# numpad.net
KiCad netlist of a schematic drawn in Altium Designer
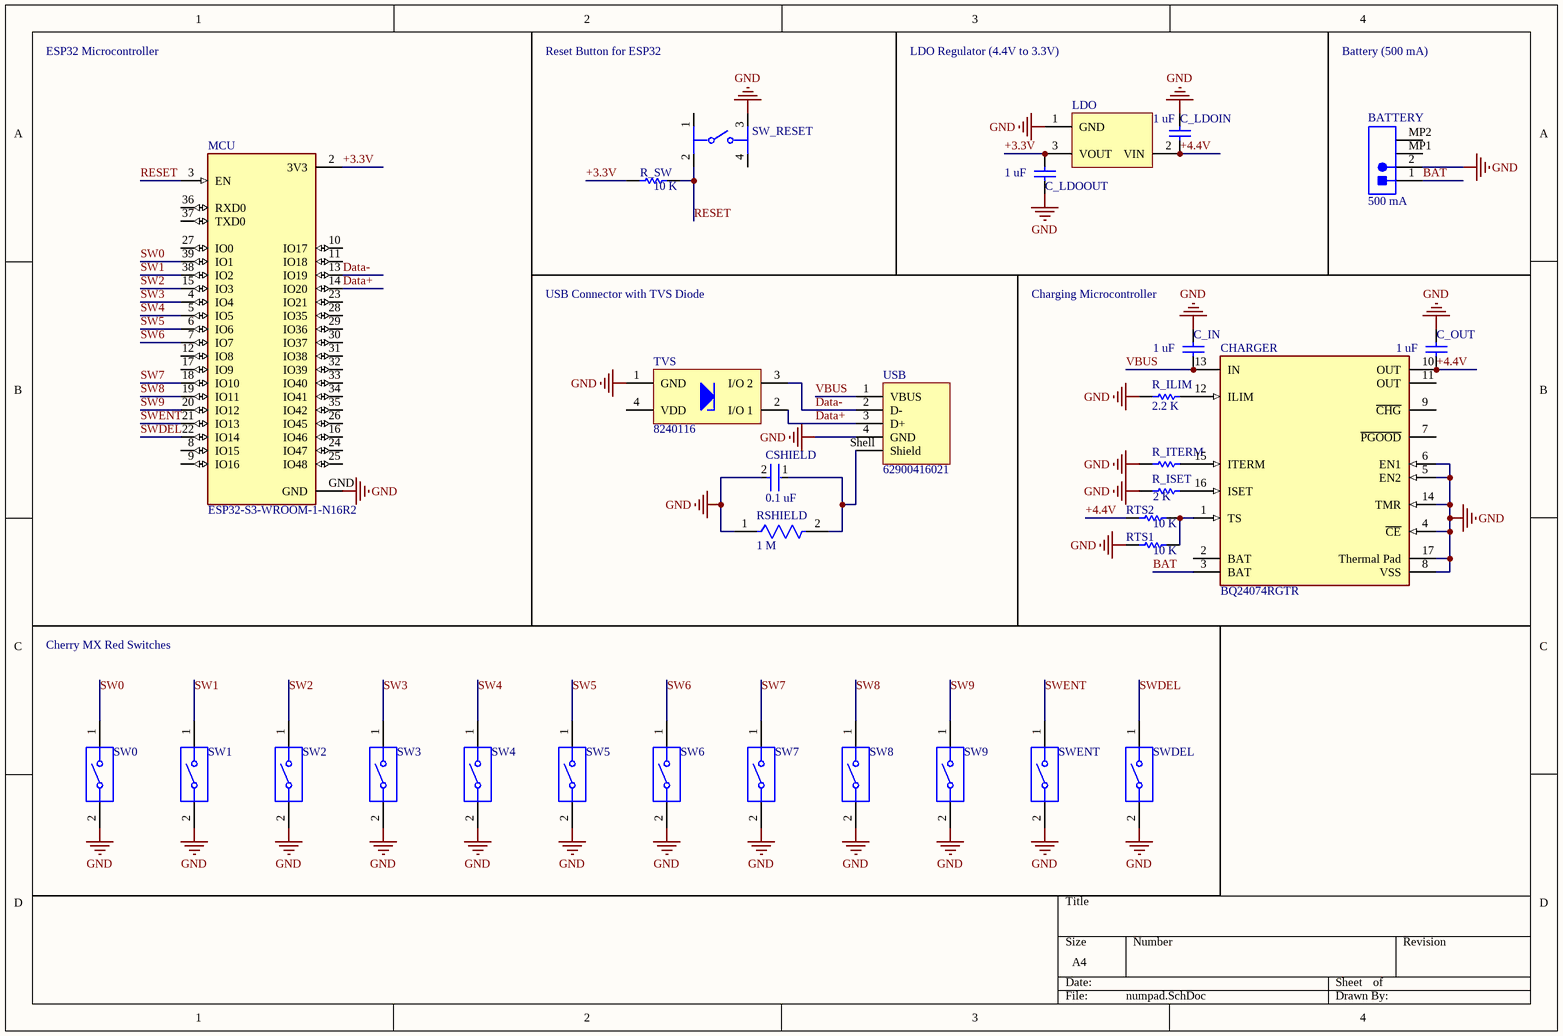
[diagram p0: numpad.SchDoc]

(export (version "E")
  (design (tool "Eeschema 10.0.6"))
  (components
    (comp (ref "BATTERY")
      (value "500 mA")
      (footprint "JST- S2B-PH-SM4-TB(LF)(SN)-2_V")
      (description "Male Header, Pitch 2 mm, 1 x 2 Position, Height 5.5 mm, -25 to 85 degC, RoHS, Tape and Reel")
      (libsource (lib "Altium Content Vault") (part "CN-1P-2M-R2"))
    )
    (comp (ref "CHARGER")
      (value "BQ24074RGTR")
      (footprint "FP-RGT0016C-IPC_B")
      (description "IC LI-ION CHARGE MGMT 16-QFN")
      (libsource (lib "Altium Content Vault") (part "bc0294d1c007ba64400ebcffad863a1"))
    )
    (comp (ref "CSHIELD")
      (value "0.1 uF")
      (footprint "FP-GRM15-MFG")
      (description "CAP CER 0.1UF 16V X7R 0402")
      (fields (field (name "MANUFACTURER PART NUMBER") "GRM155R71C104KA88D") (field (name "TOLERANCE") "10%"))
      (libsource (lib "Altium Content Vault") (part "236180d848d6139a670b325ea6854c9"))
    )
    (comp (ref "C_IN")
      (value "1 uF")
      (footprint "CAPC1608X87X35LL15T15")
      (fields (field (name "PART NUMBER") "C0603C105K3RACTU") (field (name "MANUFACTURER") "Kemet"))
      (libsource (lib "Altium Content Vault") (part "CAP"))
    )
    (comp (ref "C_LDOIN")
      (value "1 uF")
      (footprint "CAPC1608X87X35LL15T15")
      (fields (field (name "PART NUMBER") "C0603C105K3RACTU") (field (name "MANUFACTURER") "Kemet"))
      (libsource (lib "Altium Content Vault") (part "CAP"))
    )
    (comp (ref "C_LDOOUT")
      (value "1 uF")
      (footprint "CAPC1608X87X35LL15T15")
      (fields (field (name "PART NUMBER") "C0603C105K3RACTU") (field (name "MANUFACTURER") "Kemet"))
      (libsource (lib "Altium Content Vault") (part "CAP"))
    )
    (comp (ref "C_OUT")
      (value "1 uF")
      (footprint "CAPC1608X87X35LL15T15")
      (fields (field (name "PART NUMBER") "C0603C105K3RACTU") (field (name "MANUFACTURER") "Kemet"))
      (libsource (lib "Altium Content Vault") (part "CAP"))
    )
    (comp (ref "LDO")
      (value "MCP1700-3302E/TO")
      (footprint "TO-92-TO3")
      (description "Low Quiescent Current LDO, 3-Pin TO-92, Extended TemperatureBAG")
      (libsource (lib "Altium Content Vault") (part "PM-LINEREG-MCP1700-IL3B"))
    )
    (comp (ref "MCU")
      (value "ESP32-S3-WROOM-1-N16R2")
      (footprint "XCVR_ESP32-S3-WROOM-1-N16R2")
      (description "Bluetooth, WiFi 802.11b/g/n, Bluetooth v5.0 Transceiver Module 2.4GHz PCB Trace Surface Mount")
      (fields (field (name "MF") "Espressif Systems") (field (name "MP") "ESP32S3WROOM1N16R2"))
      (libsource (lib "Awab Choudhury") (part "ESP32-S3-WROOM-1-N16R2"))
    )
    (comp (ref "RSHIELD")
      (value "1 M")
      (footprint "FP-MCR01-IPC_A")
      (description "Thick Film Chip Resistor, 0402, 1MΩ, 5%, 200ppm/°C, 0.063W, 50V")
      (fields (field (name "TOLERANCE") "5%"))
      (libsource (lib "Altium Content Vault") (part "1029c3af85768c4190bb7ad29bc67b5"))
    )
    (comp (ref "RTS1")
      (value "10 K")
      (footprint "RESC1005X40X25LL05T10")
      (fields (field (name "PART NUMBER") "RC0402FR-0710KL") (field (name "MANUFACTURER") "Yageo / Phycomp"))
      (libsource (lib "Altium Content Vault") (part "RES"))
    )
    (comp (ref "RTS2")
      (value "10 K")
      (footprint "RESC1005X40X25LL05T10")
      (fields (field (name "PART NUMBER") "RC0402FR-0710KL") (field (name "MANUFACTURER") "Yageo / Phycomp"))
      (libsource (lib "Altium Content Vault") (part "RES"))
    )
    (comp (ref "R_ILIM")
      (value "2.2 K")
      (footprint "RESC1608X55X25LL10T15")
      (fields (field (name "TOLERANCE") "1%") (field (name "MANUFACTURER") "Yageo"))
      (libsource (lib "Altium Content Vault") (part "RES-2"))
    )
    (comp (ref "R_ISET")
      (value "CRCW")
      (footprint "RESC1609X50X30ML10T20")
      (fields (field (name "MANUFACTURER") "Vishay Dale") (field (name "PART NUMBER") "2 K"))
      (libsource (lib "Altium Content Vault") (part "RES"))
    )
    (comp (ref "R_ITERM")
      (value "RC04")
      (footprint "RESC1005X40X25LL05T10")
      (fields (field (name "PART NUMBER") "RC0402FR-0710KL") (field (name "MANUFACTURER") "Yageo / Phycomp"))
      (libsource (lib "Altium Content Vault") (part "RES"))
    )
    (comp (ref "R_SW")
      (value "10 K")
      (footprint "RESC1005X40X25LL05T10")
      (fields (field (name "PART NUMBER") "RC0402FR-0710KL") (field (name "MANUFACTURER") "Yageo / Phycomp"))
      (libsource (lib "Altium Content Vault") (part "RES"))
    )
    (comp (ref "SW0")
      (value "MX1A-11NW")
      (footprint "CHRY-MX1A-11NW_V")
      (description "Keylock Switch, 12 V, -10 to 70 degC, 2-Pin THD, RoHS, Bulk")
      (fields (field (name "MANUFACTURER") "Cherry") (field (name "PART NO") "MX1A11NW"))
      (libsource (lib "Altium Content Vault") (part "KEYSW-SPST-2"))
    )
    (comp (ref "SW1")
      (value "MX1A-11NW")
      (footprint "CHRY-MX1A-11NW_V")
      (description "Keylock Switch, 12 V, -10 to 70 degC, 2-Pin THD, RoHS, Bulk")
      (fields (field (name "MANUFACTURER") "Cherry") (field (name "PART NO") "MX1A11NW"))
      (libsource (lib "Altium Content Vault") (part "KEYSW-SPST-2"))
    )
    (comp (ref "SW2")
      (value "MX1A-11NW")
      (footprint "CHRY-MX1A-11NW_V")
      (description "Keylock Switch, 12 V, -10 to 70 degC, 2-Pin THD, RoHS, Bulk")
      (fields (field (name "MANUFACTURER") "Cherry") (field (name "PART NO") "MX1A11NW"))
      (libsource (lib "Altium Content Vault") (part "KEYSW-SPST-2"))
    )
    (comp (ref "SW3")
      (value "MX1A-11NW")
      (footprint "CHRY-MX1A-11NW_V")
      (description "Keylock Switch, 12 V, -10 to 70 degC, 2-Pin THD, RoHS, Bulk")
      (fields (field (name "MANUFACTURER") "Cherry") (field (name "PART NO") "MX1A11NW"))
      (libsource (lib "Altium Content Vault") (part "KEYSW-SPST-2"))
    )
    (comp (ref "SW4")
      (value "MX1A-11NW")
      (footprint "CHRY-MX1A-11NW_V")
      (description "Keylock Switch, 12 V, -10 to 70 degC, 2-Pin THD, RoHS, Bulk")
      (fields (field (name "MANUFACTURER") "Cherry") (field (name "PART NO") "MX1A11NW"))
      (libsource (lib "Altium Content Vault") (part "KEYSW-SPST-2"))
    )
    (comp (ref "SW5")
      (value "MX1A-11NW")
      (footprint "CHRY-MX1A-11NW_V")
      (description "Keylock Switch, 12 V, -10 to 70 degC, 2-Pin THD, RoHS, Bulk")
      (fields (field (name "MANUFACTURER") "Cherry") (field (name "PART NO") "MX1A11NW"))
      (libsource (lib "Altium Content Vault") (part "KEYSW-SPST-2"))
    )
    (comp (ref "SW6")
      (value "MX1A-11NW")
      (footprint "CHRY-MX1A-11NW_V")
      (description "Keylock Switch, 12 V, -10 to 70 degC, 2-Pin THD, RoHS, Bulk")
      (fields (field (name "MANUFACTURER") "Cherry") (field (name "PART NO") "MX1A11NW"))
      (libsource (lib "Altium Content Vault") (part "KEYSW-SPST-2"))
    )
    (comp (ref "SW7")
      (value "MX1A-11NW")
      (footprint "CHRY-MX1A-11NW_V")
      (description "Keylock Switch, 12 V, -10 to 70 degC, 2-Pin THD, RoHS, Bulk")
      (fields (field (name "MANUFACTURER") "Cherry") (field (name "PART NO") "MX1A11NW"))
      (libsource (lib "Altium Content Vault") (part "KEYSW-SPST-2"))
    )
    (comp (ref "SW8")
      (value "MX1A-11NW")
      (footprint "CHRY-MX1A-11NW_V")
      (description "Keylock Switch, 12 V, -10 to 70 degC, 2-Pin THD, RoHS, Bulk")
      (fields (field (name "MANUFACTURER") "Cherry") (field (name "PART NO") "MX1A11NW"))
      (libsource (lib "Altium Content Vault") (part "KEYSW-SPST-2"))
    )
    (comp (ref "SW9")
      (value "MX1A-11NW")
      (footprint "CHRY-MX1A-11NW_V")
      (description "Keylock Switch, 12 V, -10 to 70 degC, 2-Pin THD, RoHS, Bulk")
      (fields (field (name "MANUFACTURER") "Cherry") (field (name "PART NO") "MX1A11NW"))
      (libsource (lib "Altium Content Vault") (part "KEYSW-SPST-2"))
    )
    (comp (ref "SWDEL")
      (value "MX1A-11NW")
      (footprint "CHRY-MX1A-11NW_V")
      (description "Keylock Switch, 12 V, -10 to 70 degC, 2-Pin THD, RoHS, Bulk")
      (fields (field (name "MANUFACTURER") "Cherry") (field (name "PART NO") "MX1A11NW"))
      (libsource (lib "Altium Content Vault") (part "KEYSW-SPST-2"))
    )
    (comp (ref "SWENT")
      (value "MX1A-11NW")
      (footprint "CHRY-MX1A-11NW_V")
      (description "Keylock Switch, 12 V, -10 to 70 degC, 2-Pin THD, RoHS, Bulk")
      (fields (field (name "MANUFACTURER") "Cherry") (field (name "PART NO") "MX1A11NW"))
      (libsource (lib "Altium Content Vault") (part "KEYSW-SPST-2"))
    )
    (comp (ref "SW_RESET")
      (value "3-1825910-1")
      (footprint "FP-3-1825910-1-MFG")
      (description "SWITCH TACTILE SPST-NO 0.05A 24V")
      (fields
        (field (name "MANUFACTURER") "TE Connectivity")
        (field (name "OCTOPART") "https://octopart.com/3-1825910-1-te+connectivity-46506874")
      )
      (libsource (lib "Altium Content Vault") (part "b8895f3f4cefb76e1819d2863dba89b"))
    )
    (comp (ref "TVS")
      (value "8240116")
      (footprint "WE-TVS_SOT143-4L")
      (libsource (lib "Altium Content Vault") (part "Diode_2+1 Channel_Unidirectional - 8240116"))
    )
    (comp (ref "USB")
      (value "62900416021")
      (footprint "62900416021")
      (libsource (lib "Altium Content Vault") (part "USB 2.0_Type A_Receptacle_1 Port"))
    )
  )
  (nets
    (net (code "1") (name "/+3.3V") (class "Default")
      (node (ref "C_LDOOUT") (pin "2") (pinfunction "2_2") (pintype "passive"))
      (node (ref "LDO") (pin "3") (pinfunction "VOUT_3") (pintype "power_in"))
      (node (ref "MCU") (pin "2") (pinfunction "3V3_2") (pintype "power_in"))
      (node (ref "R_SW") (pin "1") (pinfunction "1_1") (pintype "passive"))
    )
    (net (code "2") (name "/+4.4V") (class "Default")
      (node (ref "CHARGER") (pin "10") (pinfunction "OUT_10") (pintype "power_in"))
      (node (ref "C_LDOIN") (pin "1") (pinfunction "1_1") (pintype "passive"))
      (node (ref "C_OUT") (pin "1") (pinfunction "1_1") (pintype "passive"))
      (node (ref "LDO") (pin "2") (pinfunction "VIN_2") (pintype "power_in"))
      (node (ref "RTS2") (pin "1") (pinfunction "1_1") (pintype "passive"))
    )
    (net (code "3") (name "/BAT") (class "Default")
      (node (ref "BATTERY") (pin "1") (pinfunction "1_1") (pintype "passive"))
      (node (ref "CHARGER") (pin "3") (pinfunction "BAT_3") (pintype "power_in"))
    )
    (net (code "4") (name "/Data+") (class "Default")
      (node (ref "MCU") (pin "14") (pinfunction "IO20_14") (pintype "bidirectional"))
      (node (ref "TVS") (pin "2") (pinfunction "I/O_1_2") (pintype "passive"))
      (node (ref "USB") (pin "3") (pinfunction "D+_3") (pintype "passive"))
    )
    (net (code "5") (name "/Data-") (class "Default")
      (node (ref "MCU") (pin "13") (pinfunction "IO19_13") (pintype "bidirectional"))
      (node (ref "TVS") (pin "3") (pinfunction "I/O_2_3") (pintype "passive"))
      (node (ref "USB") (pin "2") (pinfunction "D-_2") (pintype "passive"))
    )
    (net (code "6") (name "/RESET") (class "Default")
      (node (ref "MCU") (pin "3") (pinfunction "EN_3") (pintype "input"))
      (node (ref "R_SW") (pin "2") (pinfunction "2_2") (pintype "passive"))
      (node (ref "SW_RESET") (pin "2") (pinfunction "2_2") (pintype "passive"))
    )
    (net (code "7") (name "/SW0") (class "Default")
      (node (ref "MCU") (pin "39") (pinfunction "IO1_39") (pintype "bidirectional"))
      (node (ref "SW0") (pin "1") (pinfunction "1_1") (pintype "passive"))
    )
    (net (code "8") (name "/SW1") (class "Default")
      (node (ref "MCU") (pin "38") (pinfunction "IO2_38") (pintype "bidirectional"))
      (node (ref "SW1") (pin "1") (pinfunction "1_1") (pintype "passive"))
    )
    (net (code "9") (name "/SW2") (class "Default")
      (node (ref "MCU") (pin "15") (pinfunction "IO3_15") (pintype "bidirectional"))
      (node (ref "SW2") (pin "1") (pinfunction "1_1") (pintype "passive"))
    )
    (net (code "10") (name "/SW3") (class "Default")
      (node (ref "MCU") (pin "4") (pinfunction "IO4_4") (pintype "bidirectional"))
      (node (ref "SW3") (pin "1") (pinfunction "1_1") (pintype "passive"))
    )
    (net (code "11") (name "/SW4") (class "Default")
      (node (ref "MCU") (pin "5") (pinfunction "IO5_5") (pintype "bidirectional"))
      (node (ref "SW4") (pin "1") (pinfunction "1_1") (pintype "passive"))
    )
    (net (code "12") (name "/SW5") (class "Default")
      (node (ref "MCU") (pin "6") (pinfunction "IO6_6") (pintype "bidirectional"))
      (node (ref "SW5") (pin "1") (pinfunction "1_1") (pintype "passive"))
    )
    (net (code "13") (name "/SW6") (class "Default")
      (node (ref "MCU") (pin "7") (pinfunction "IO7_7") (pintype "bidirectional"))
      (node (ref "SW6") (pin "1") (pinfunction "1_1") (pintype "passive"))
    )
    (net (code "14") (name "/SW7") (class "Default")
      (node (ref "MCU") (pin "18") (pinfunction "IO10_18") (pintype "bidirectional"))
      (node (ref "SW7") (pin "1") (pinfunction "1_1") (pintype "passive"))
    )
    (net (code "15") (name "/SW8") (class "Default")
      (node (ref "MCU") (pin "19") (pinfunction "IO11_19") (pintype "bidirectional"))
      (node (ref "SW8") (pin "1") (pinfunction "1_1") (pintype "passive"))
    )
    (net (code "16") (name "/SW9") (class "Default")
      (node (ref "MCU") (pin "20") (pinfunction "IO12_20") (pintype "bidirectional"))
      (node (ref "SW9") (pin "1") (pinfunction "1_1") (pintype "passive"))
    )
    (net (code "17") (name "/SWDEL") (class "Default")
      (node (ref "MCU") (pin "22") (pinfunction "IO14_22") (pintype "bidirectional"))
      (node (ref "SWDEL") (pin "1") (pinfunction "1_1") (pintype "passive"))
    )
    (net (code "18") (name "/SWENT") (class "Default")
      (node (ref "MCU") (pin "21") (pinfunction "IO13_21") (pintype "bidirectional"))
      (node (ref "SWENT") (pin "1") (pinfunction "1_1") (pintype "passive"))
    )
    (net (code "19") (name "/VBUS") (class "Default")
      (node (ref "CHARGER") (pin "13") (pinfunction "IN_13") (pintype "power_in"))
      (node (ref "C_IN") (pin "1") (pinfunction "1_1") (pintype "passive"))
      (node (ref "USB") (pin "1") (pinfunction "VBUS_1") (pintype "passive"))
    )
    (net (code "20") (name "GND") (class "Default")
      (node (ref "BATTERY") (pin "2") (pinfunction "2_2") (pintype "passive"))
      (node (ref "CHARGER") (pin "14") (pinfunction "TMR_14") (pintype "input"))
      (node (ref "CHARGER") (pin "17") (pinfunction "Thermal_Pad_17") (pintype "power_in"))
      (node (ref "CHARGER") (pin "4") (pinfunction "~{CE}_4") (pintype "input"))
      (node (ref "CHARGER") (pin "5") (pinfunction "EN2_5") (pintype "input"))
      (node (ref "CHARGER") (pin "6") (pinfunction "EN1_6") (pintype "input"))
      (node (ref "CHARGER") (pin "8") (pinfunction "VSS_8") (pintype "power_in"))
      (node (ref "CSHIELD") (pin "2") (pinfunction "2_2") (pintype "passive"))
      (node (ref "C_IN") (pin "2") (pinfunction "2_2") (pintype "passive"))
      (node (ref "C_LDOIN") (pin "2") (pinfunction "2_2") (pintype "passive"))
      (node (ref "C_LDOOUT") (pin "1") (pinfunction "1_1") (pintype "passive"))
      (node (ref "C_OUT") (pin "2") (pinfunction "2_2") (pintype "passive"))
      (node (ref "LDO") (pin "1") (pinfunction "GND_1") (pintype "power_in"))
      (node (ref "MCU") (pin "GND") (pinfunction "GND_GND") (pintype "power_in"))
      (node (ref "RSHIELD") (pin "1") (pinfunction "1_1") (pintype "passive"))
      (node (ref "RTS1") (pin "1") (pinfunction "1_1") (pintype "passive"))
      (node (ref "R_ILIM") (pin "1") (pinfunction "1_1") (pintype "passive"))
      (node (ref "R_ISET") (pin "1") (pinfunction "1_1") (pintype "passive"))
      (node (ref "R_ITERM") (pin "1") (pinfunction "1_1") (pintype "passive"))
      (node (ref "SW0") (pin "2") (pinfunction "2_2") (pintype "passive"))
      (node (ref "SW1") (pin "2") (pinfunction "2_2") (pintype "passive"))
      (node (ref "SW2") (pin "2") (pinfunction "2_2") (pintype "passive"))
      (node (ref "SW3") (pin "2") (pinfunction "2_2") (pintype "passive"))
      (node (ref "SW4") (pin "2") (pinfunction "2_2") (pintype "passive"))
      (node (ref "SW5") (pin "2") (pinfunction "2_2") (pintype "passive"))
      (node (ref "SW6") (pin "2") (pinfunction "2_2") (pintype "passive"))
      (node (ref "SW7") (pin "2") (pinfunction "2_2") (pintype "passive"))
      (node (ref "SW8") (pin "2") (pinfunction "2_2") (pintype "passive"))
      (node (ref "SW9") (pin "2") (pinfunction "2_2") (pintype "passive"))
      (node (ref "SWDEL") (pin "2") (pinfunction "2_2") (pintype "passive"))
      (node (ref "SWENT") (pin "2") (pinfunction "2_2") (pintype "passive"))
      (node (ref "SW_RESET") (pin "3") (pinfunction "3_3") (pintype "passive"))
      (node (ref "TVS") (pin "1") (pinfunction "GND_1") (pintype "passive"))
      (node (ref "USB") (pin "4") (pinfunction "GND_4") (pintype "passive"))
    )
    (net (code "21") (name "Net-(CHARGER-ILIM)") (class "Default")
      (node (ref "CHARGER") (pin "12") (pinfunction "ILIM_12") (pintype "input"))
      (node (ref "R_ILIM") (pin "2") (pinfunction "2_2") (pintype "passive"))
    )
    (net (code "22") (name "Net-(CHARGER-ISET)") (class "Default")
      (node (ref "CHARGER") (pin "16") (pinfunction "ISET_16") (pintype "input"))
      (node (ref "R_ISET") (pin "2") (pinfunction "2_2") (pintype "passive"))
    )
    (net (code "23") (name "Net-(CHARGER-ITERM)") (class "Default")
      (node (ref "CHARGER") (pin "15") (pinfunction "ITERM_15") (pintype "input"))
      (node (ref "R_ITERM") (pin "2") (pinfunction "2_2") (pintype "passive"))
    )
    (net (code "24") (name "Net-(CHARGER-TS)") (class "Default")
      (node (ref "CHARGER") (pin "1") (pinfunction "TS_1") (pintype "input"))
      (node (ref "RTS1") (pin "2") (pinfunction "2_2") (pintype "passive"))
      (node (ref "RTS2") (pin "2") (pinfunction "2_2") (pintype "passive"))
    )
    (net (code "25") (name "Net-(USB-Shield)") (class "Default")
      (node (ref "CSHIELD") (pin "1") (pinfunction "1_1") (pintype "passive"))
      (node (ref "RSHIELD") (pin "2") (pinfunction "2_2") (pintype "passive"))
      (node (ref "USB") (pin "Shell") (pinfunction "Shield_Shell") (pintype "passive"))
    )
    (net (code "26") (name "unconnected-(BATTERY-PadMP1)") (class "Default")
      (node (ref "BATTERY") (pin "MP1") (pinfunction "MP1_MP1") (pintype "passive"))
    )
    (net (code "27") (name "unconnected-(BATTERY-PadMP2)") (class "Default")
      (node (ref "BATTERY") (pin "MP2") (pinfunction "MP2_MP2") (pintype "passive"))
    )
    (net (code "28") (name "unconnected-(CHARGER-BAT-Pad2)") (class "Default")
      (node (ref "CHARGER") (pin "2") (pinfunction "BAT_2") (pintype "power_in"))
    )
    (net (code "29") (name "unconnected-(CHARGER-OUT-Pad11)") (class "Default")
      (node (ref "CHARGER") (pin "11") (pinfunction "OUT_11") (pintype "power_in"))
    )
    (net (code "30") (name "unconnected-(CHARGER-~{CHG}-Pad9)") (class "Default")
      (node (ref "CHARGER") (pin "9") (pinfunction "~{CHG}_9") (pintype "tri_state"))
    )
    (net (code "31") (name "unconnected-(CHARGER-~{PGOOD}-Pad7)") (class "Default")
      (node (ref "CHARGER") (pin "7") (pinfunction "~{PGOOD}_7") (pintype "tri_state"))
    )
    (net (code "32") (name "unconnected-(MCU-IO0-Pad27)") (class "Default")
      (node (ref "MCU") (pin "27") (pinfunction "IO0_27") (pintype "bidirectional"))
    )
    (net (code "33") (name "unconnected-(MCU-IO8-Pad12)") (class "Default")
      (node (ref "MCU") (pin "12") (pinfunction "IO8_12") (pintype "bidirectional"))
    )
    (net (code "34") (name "unconnected-(MCU-IO9-Pad17)") (class "Default")
      (node (ref "MCU") (pin "17") (pinfunction "IO9_17") (pintype "bidirectional"))
    )
    (net (code "35") (name "unconnected-(MCU-IO15-Pad8)") (class "Default")
      (node (ref "MCU") (pin "8") (pinfunction "IO15_8") (pintype "bidirectional"))
    )
    (net (code "36") (name "unconnected-(MCU-IO16-Pad9)") (class "Default")
      (node (ref "MCU") (pin "9") (pinfunction "IO16_9") (pintype "bidirectional"))
    )
    (net (code "37") (name "unconnected-(MCU-IO17-Pad10)") (class "Default")
      (node (ref "MCU") (pin "10") (pinfunction "IO17_10") (pintype "bidirectional"))
    )
    (net (code "38") (name "unconnected-(MCU-IO18-Pad11)") (class "Default")
      (node (ref "MCU") (pin "11") (pinfunction "IO18_11") (pintype "bidirectional"))
    )
    (net (code "39") (name "unconnected-(MCU-IO21-Pad23)") (class "Default")
      (node (ref "MCU") (pin "23") (pinfunction "IO21_23") (pintype "bidirectional"))
    )
    (net (code "40") (name "unconnected-(MCU-IO35-Pad28)") (class "Default")
      (node (ref "MCU") (pin "28") (pinfunction "IO35_28") (pintype "bidirectional"))
    )
    (net (code "41") (name "unconnected-(MCU-IO36-Pad29)") (class "Default")
      (node (ref "MCU") (pin "29") (pinfunction "IO36_29") (pintype "bidirectional"))
    )
    (net (code "42") (name "unconnected-(MCU-IO37-Pad30)") (class "Default")
      (node (ref "MCU") (pin "30") (pinfunction "IO37_30") (pintype "bidirectional"))
    )
    (net (code "43") (name "unconnected-(MCU-IO38-Pad31)") (class "Default")
      (node (ref "MCU") (pin "31") (pinfunction "IO38_31") (pintype "bidirectional"))
    )
    (net (code "44") (name "unconnected-(MCU-IO39-Pad32)") (class "Default")
      (node (ref "MCU") (pin "32") (pinfunction "IO39_32") (pintype "bidirectional"))
    )
    (net (code "45") (name "unconnected-(MCU-IO40-Pad33)") (class "Default")
      (node (ref "MCU") (pin "33") (pinfunction "IO40_33") (pintype "bidirectional"))
    )
    (net (code "46") (name "unconnected-(MCU-IO41-Pad34)") (class "Default")
      (node (ref "MCU") (pin "34") (pinfunction "IO41_34") (pintype "bidirectional"))
    )
    (net (code "47") (name "unconnected-(MCU-IO42-Pad35)") (class "Default")
      (node (ref "MCU") (pin "35") (pinfunction "IO42_35") (pintype "bidirectional"))
    )
    (net (code "48") (name "unconnected-(MCU-IO45-Pad26)") (class "Default")
      (node (ref "MCU") (pin "26") (pinfunction "IO45_26") (pintype "bidirectional"))
    )
    (net (code "49") (name "unconnected-(MCU-IO46-Pad16)") (class "Default")
      (node (ref "MCU") (pin "16") (pinfunction "IO46_16") (pintype "bidirectional"))
    )
    (net (code "50") (name "unconnected-(MCU-IO47-Pad24)") (class "Default")
      (node (ref "MCU") (pin "24") (pinfunction "IO47_24") (pintype "bidirectional"))
    )
    (net (code "51") (name "unconnected-(MCU-IO48-Pad25)") (class "Default")
      (node (ref "MCU") (pin "25") (pinfunction "IO48_25") (pintype "bidirectional"))
    )
    (net (code "52") (name "unconnected-(MCU-RXD0-Pad36)") (class "Default")
      (node (ref "MCU") (pin "36") (pinfunction "RXD0_36") (pintype "bidirectional"))
    )
    (net (code "53") (name "unconnected-(MCU-TXD0-Pad37)") (class "Default")
      (node (ref "MCU") (pin "37") (pinfunction "TXD0_37") (pintype "bidirectional"))
    )
    (net (code "54") (name "unconnected-(SW_RESET-Pad1)") (class "Default")
      (node (ref "SW_RESET") (pin "1") (pinfunction "1_1") (pintype "passive"))
    )
    (net (code "55") (name "unconnected-(SW_RESET-Pad4)") (class "Default")
      (node (ref "SW_RESET") (pin "4") (pinfunction "4_4") (pintype "passive"))
    )
    (net (code "56") (name "unconnected-(TVS-VDD-Pad4)") (class "Default")
      (node (ref "TVS") (pin "4") (pinfunction "VDD_4") (pintype "passive"))
    )
  )
)
